# radio-v4_0.net
KiCad netlist of a schematic drawn in EAGLE
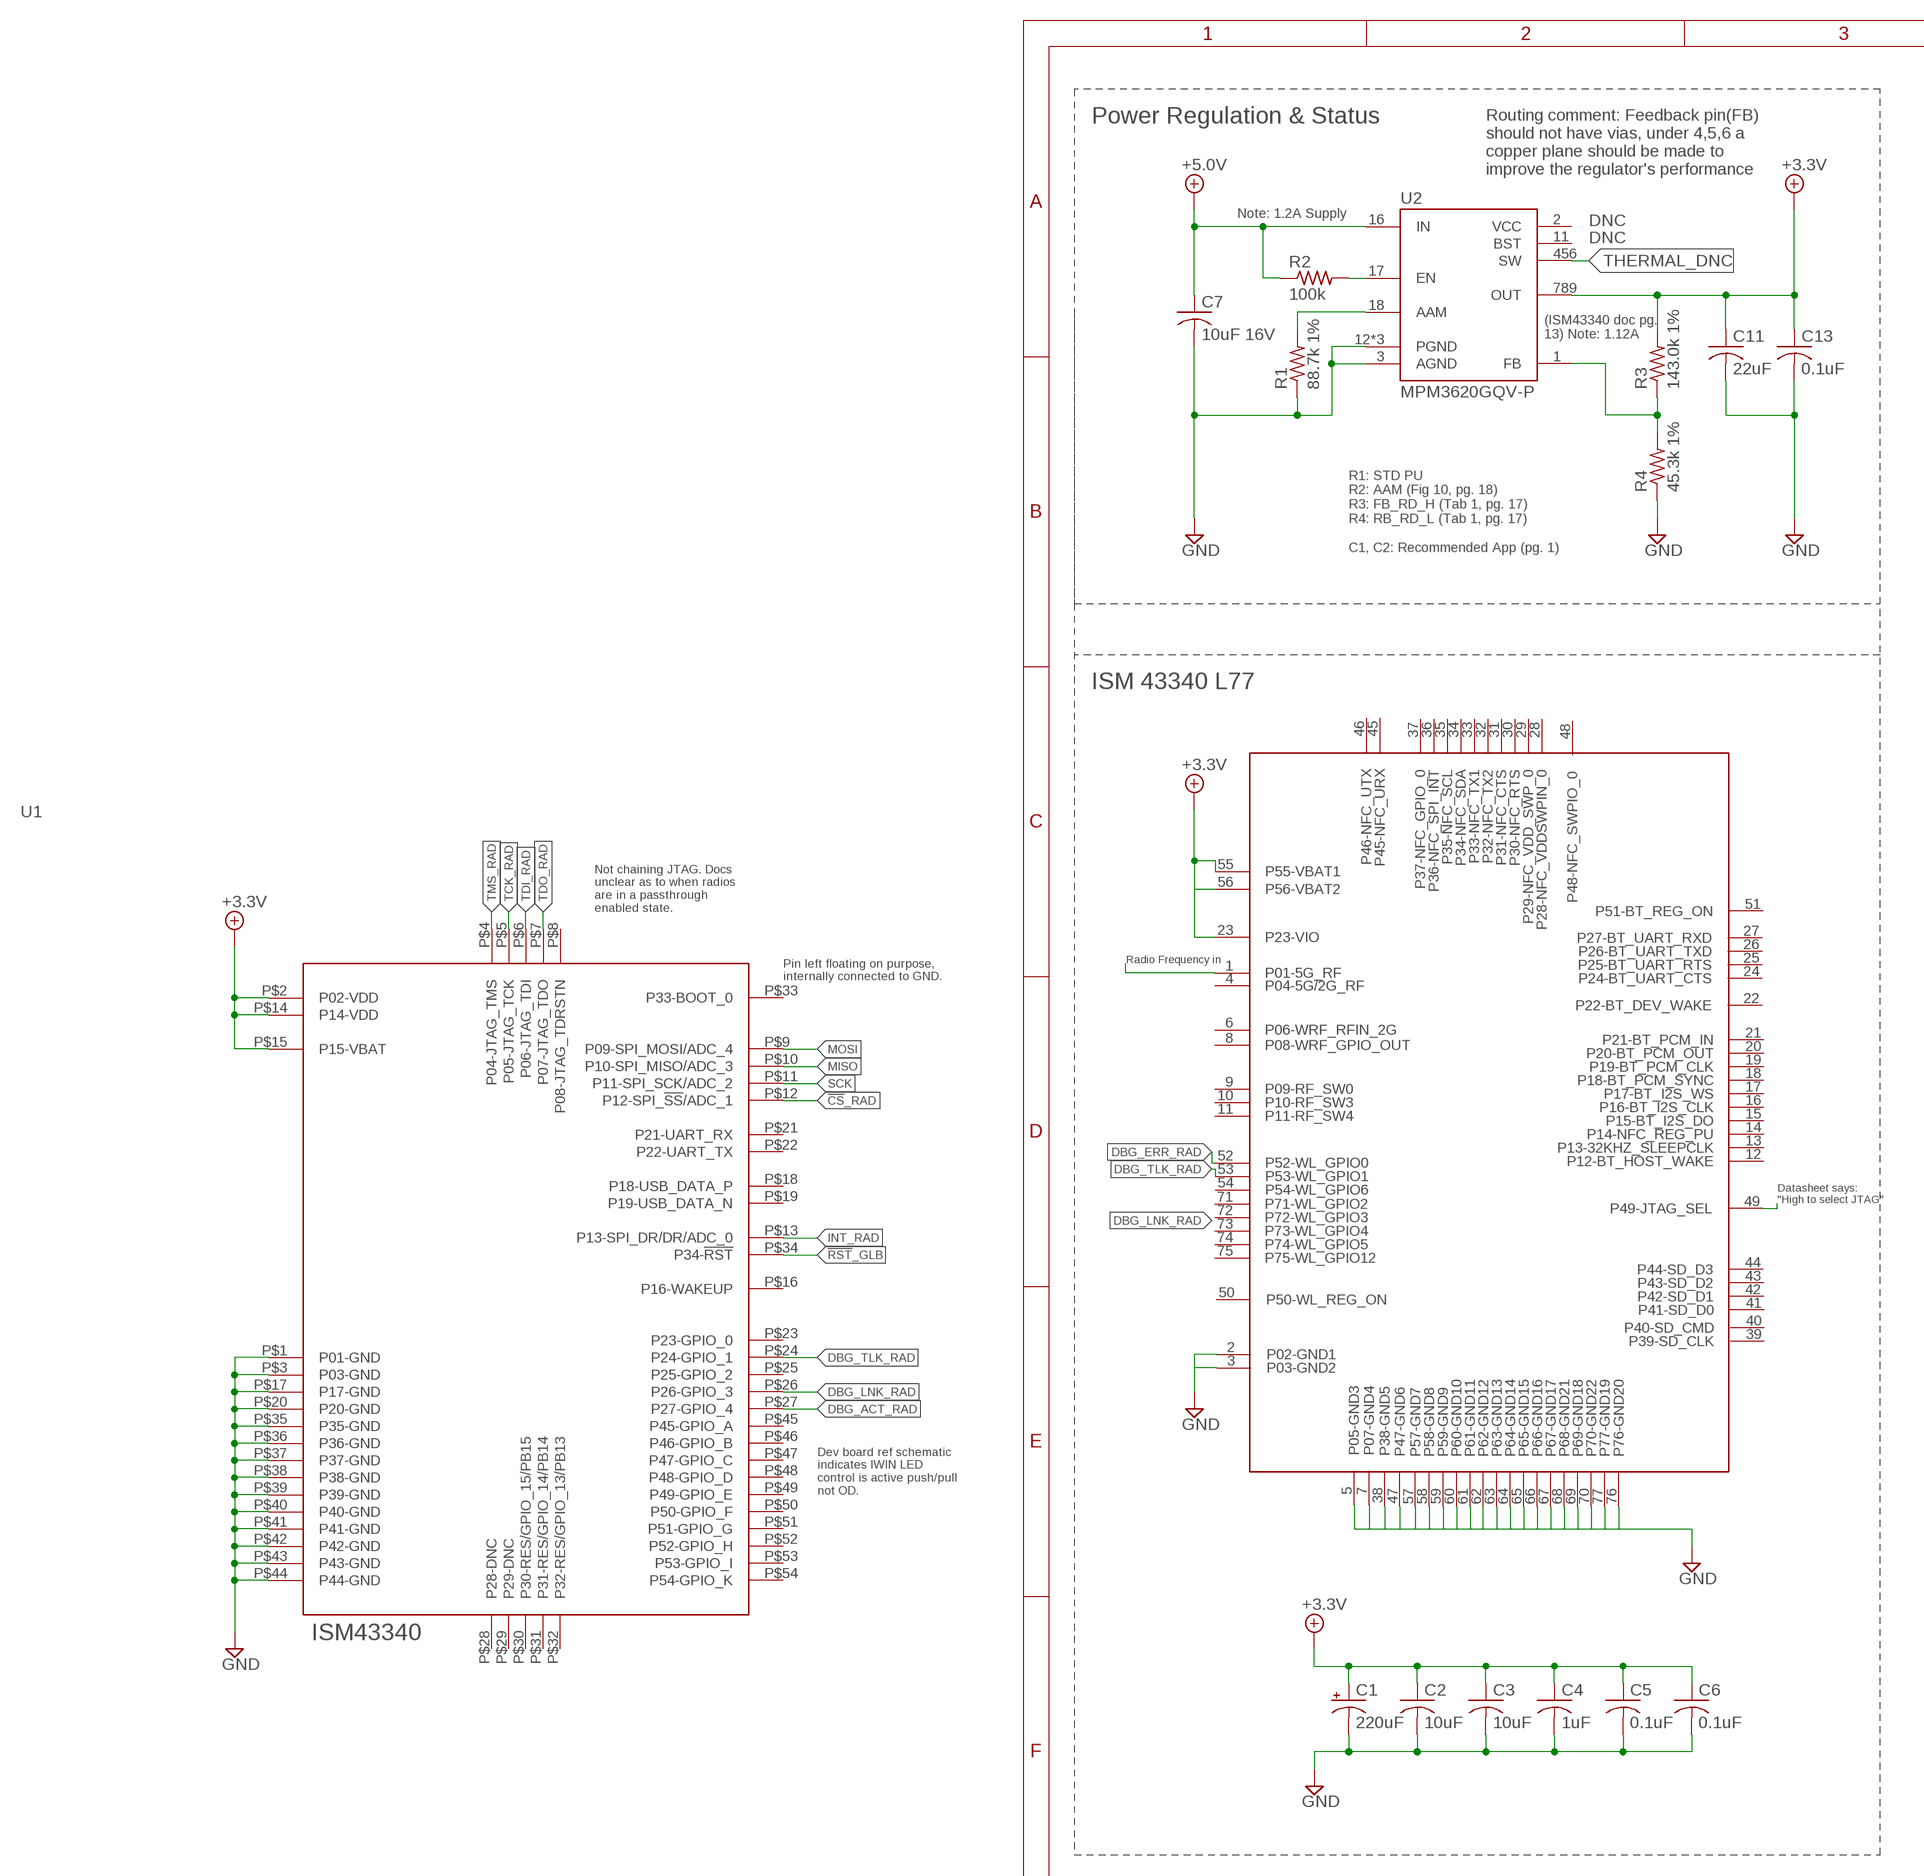
[diagram p0: schematic, sheet 1, part 1 of 2]
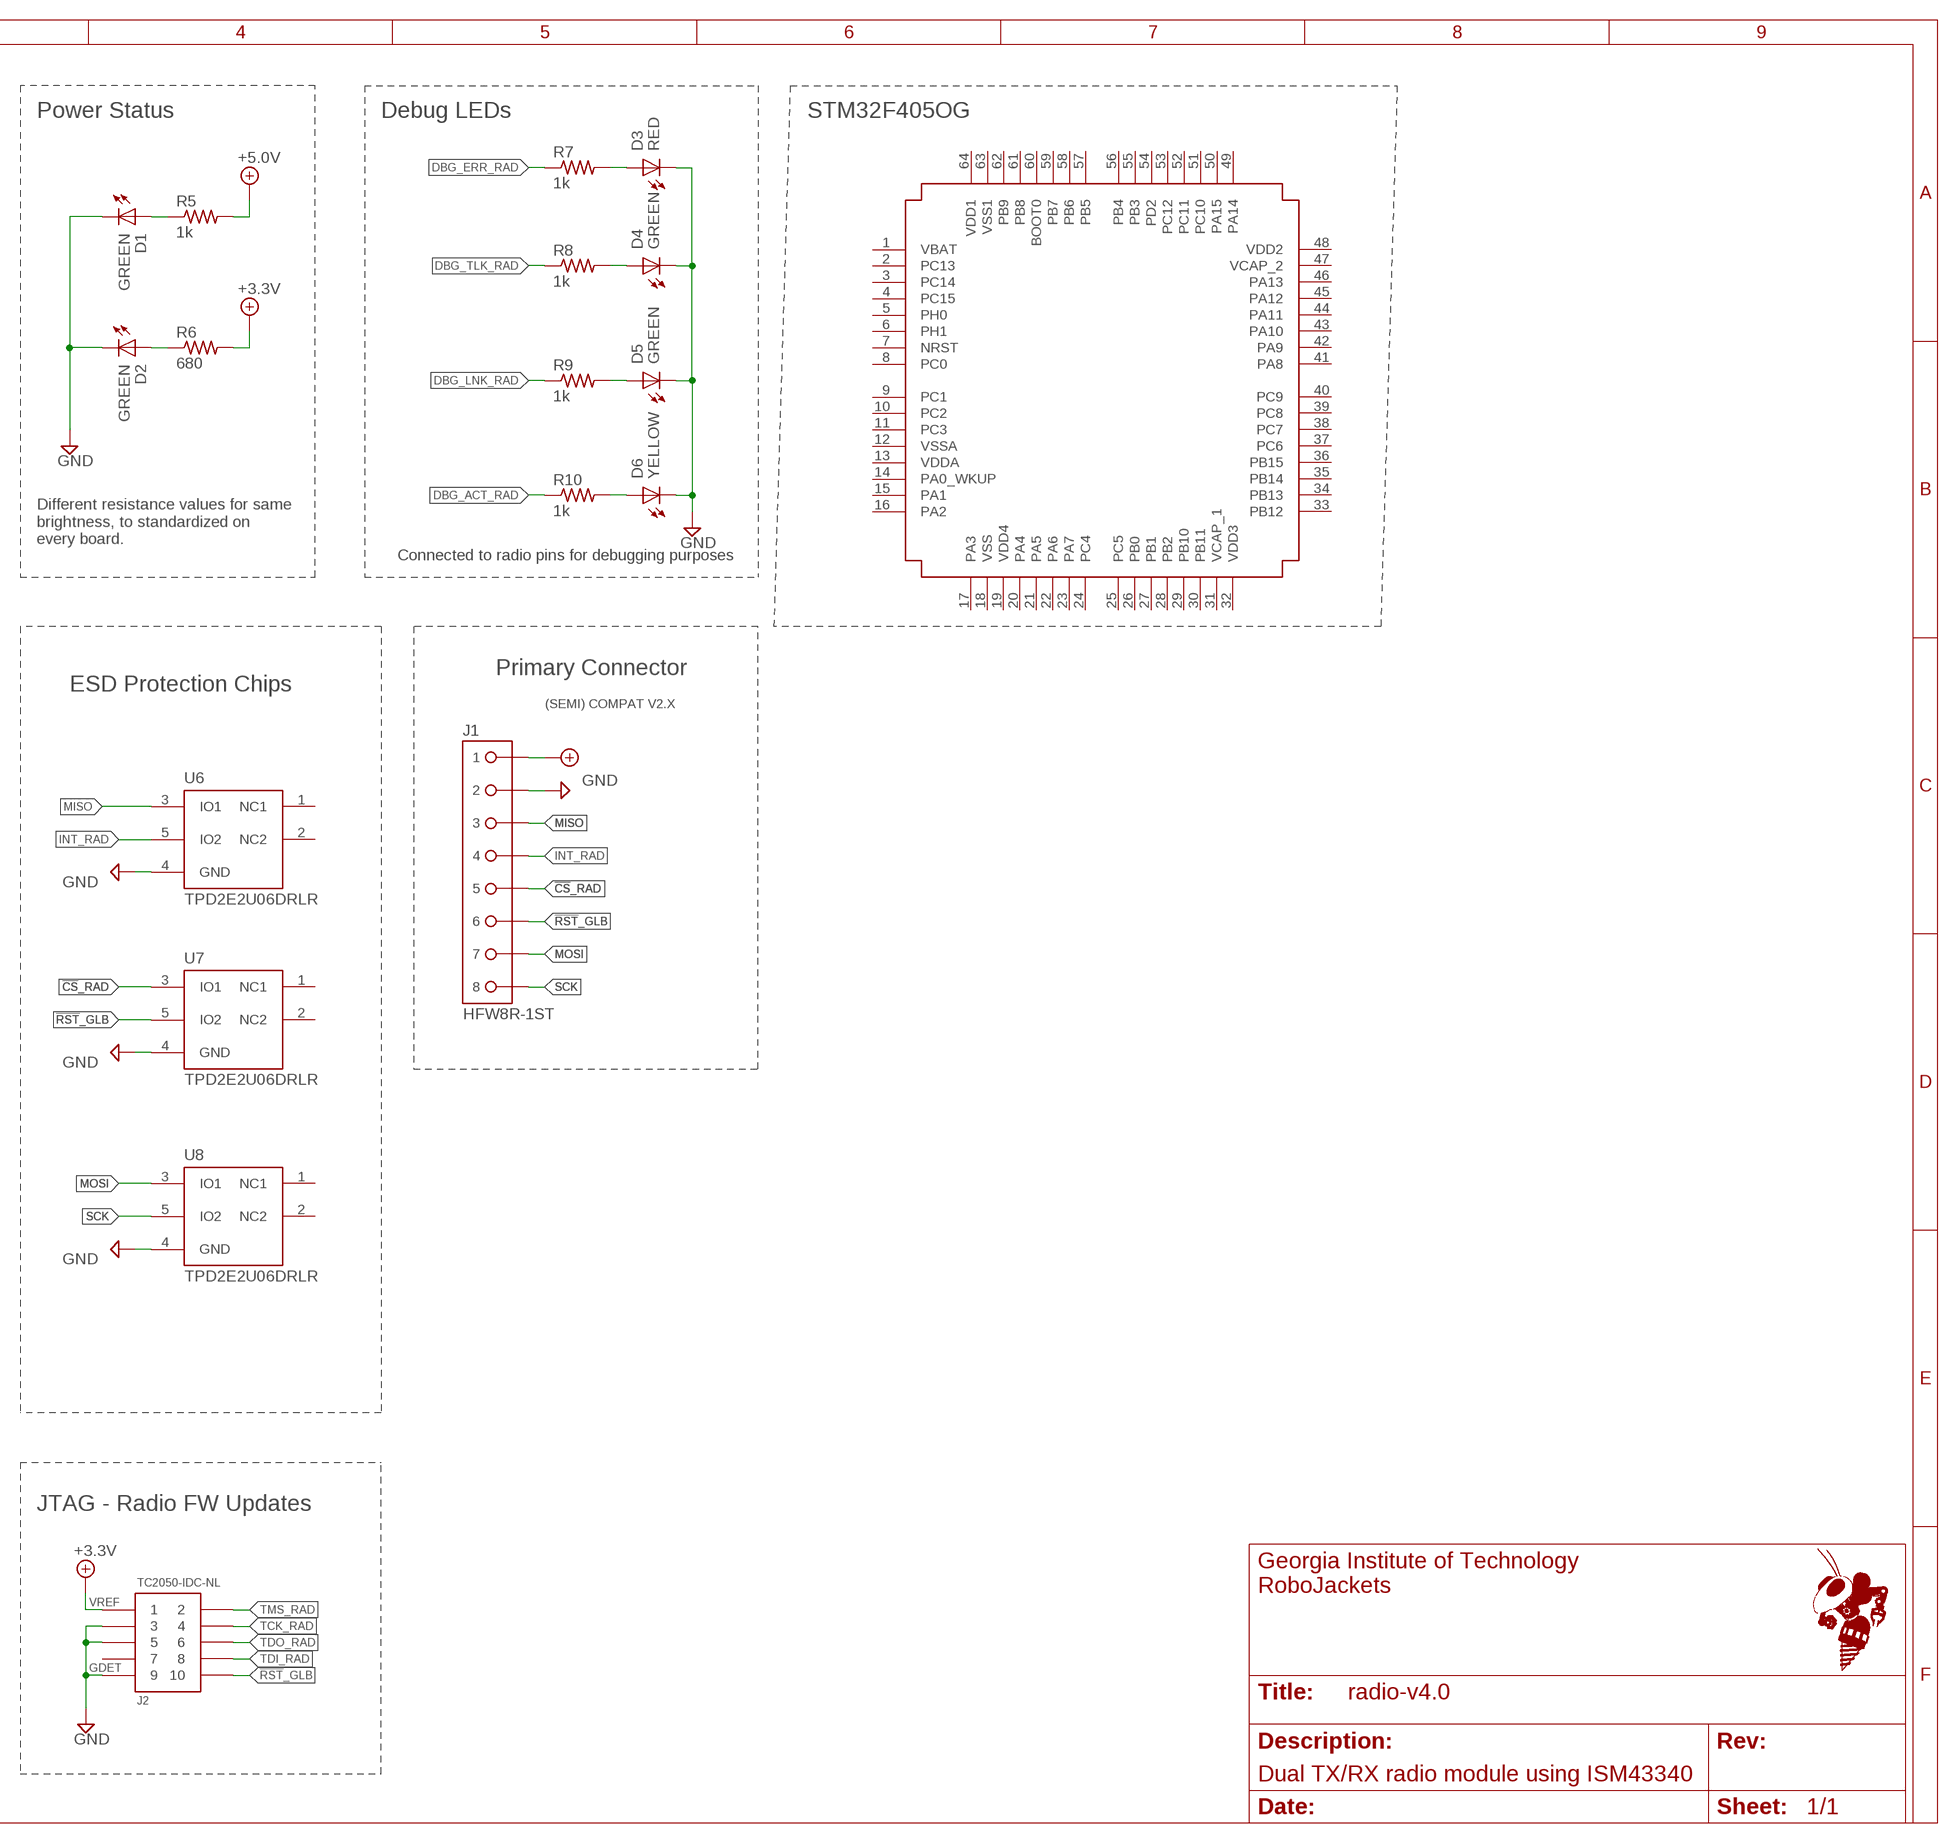
[diagram p1: schematic, sheet 1, part 2 of 2]

(export (version "E")
  (design (tool "Eeschema 10.0.6"))
  (components
    (comp (ref "C1")
      (value "220uF")
      (footprint "eagle-import:ECA-0JM221-HGT_HORIZ")
      (libsource (lib "eagle-import") (part "ECA-0JM221"))
    )
    (comp (ref "C2")
      (value "10uF")
      (footprint "eagle-import:C0805")
      (libsource (lib "eagle-import") (part "C-USC0805"))
    )
    (comp (ref "C3")
      (value "10uF")
      (footprint "eagle-import:C0805")
      (libsource (lib "eagle-import") (part "C-USC0805"))
    )
    (comp (ref "C4")
      (value "1uF")
      (footprint "eagle-import:C0603")
      (libsource (lib "eagle-import") (part "C-USC0603"))
    )
    (comp (ref "C5")
      (value "0.1uF")
      (footprint "eagle-import:C0603")
      (libsource (lib "eagle-import") (part "C-USC0603"))
    )
    (comp (ref "C6")
      (value "0.1uF")
      (footprint "eagle-import:C0603")
      (libsource (lib "eagle-import") (part "C-USC0603"))
    )
    (comp (ref "C7")
      (value "10uF 16V")
      (footprint "eagle-import:C1210")
      (libsource (lib "eagle-import") (part "C-USC1210"))
    )
    (comp (ref "C11")
      (value "22uF")
      (footprint "eagle-import:C1210")
      (libsource (lib "eagle-import") (part "C-USC1210"))
    )
    (comp (ref "C13")
      (value "0.1uF")
      (footprint "eagle-import:C0603")
      (libsource (lib "eagle-import") (part "C-USC0603"))
    )
    (comp (ref "D1")
      (value "GREEN")
      (footprint "eagle-import:CHIP-LED0603")
      (fields (field (name "MPN") "LTST-C191KGKT"))
      (libsource (lib "eagle-import") (part "LED-SMD-GREEN"))
    )
    (comp (ref "D2")
      (value "GREEN")
      (footprint "eagle-import:CHIP-LED0603")
      (fields (field (name "MPN") "LTST-C191KGKT"))
      (libsource (lib "eagle-import") (part "LED-SMD-GREEN"))
    )
    (comp (ref "D3")
      (value "RED")
      (footprint "eagle-import:CHIP-LED0603")
      (fields (field (name "MPN") "LTST-C191KRKT"))
      (libsource (lib "eagle-import") (part "LED-SMD-RED"))
    )
    (comp (ref "D4")
      (value "GREEN")
      (footprint "eagle-import:CHIP-LED0603")
      (fields (field (name "MPN") "LTST-C191KGKT"))
      (libsource (lib "eagle-import") (part "LED-SMD-GREEN"))
    )
    (comp (ref "D5")
      (value "GREEN")
      (footprint "eagle-import:CHIP-LED0603")
      (fields (field (name "MPN") "LTST-C191KGKT"))
      (libsource (lib "eagle-import") (part "LED-SMD-GREEN"))
    )
    (comp (ref "D6")
      (value "YELLOW")
      (footprint "eagle-import:CHIP-LED0603")
      (fields (field (name "MPN") "LTST-C191KSKT"))
      (libsource (lib "eagle-import") (part "LED-SMD-YELLOW"))
    )
    (comp (ref "J1")
      (value "HFW8R-1ST")
      (footprint "eagle-import:HFW8R-1ST")
      (fields (field (name "MPN") "HFW8R-1STE1LF"))
      (libsource (lib "eagle-import") (part "HFW8R-1ST"))
    )
    (comp (ref "J2")
      (value "TC2050-IDC-NL")
      (footprint "eagle-import:TC2050-IDC-NL")
      (libsource (lib "eagle-import") (part "TC2050-IDC-NL"))
    )
    (comp (ref "R1")
      (value "88.7k 1%")
      (footprint "eagle-import:R0603")
      (libsource (lib "eagle-import") (part "resistor_348_R-US_R0603"))
    )
    (comp (ref "R2")
      (value "100k")
      (footprint "eagle-import:R0603")
      (libsource (lib "eagle-import") (part "resistor_348_R-US_R0603"))
    )
    (comp (ref "R3")
      (value "143.0k 1%")
      (footprint "eagle-import:R0603")
      (libsource (lib "eagle-import") (part "R-US_R0603"))
    )
    (comp (ref "R4")
      (value "45.3k 1%")
      (footprint "eagle-import:R0603")
      (libsource (lib "eagle-import") (part "R-US_R0603"))
    )
    (comp (ref "R5")
      (value "1k")
      (footprint "eagle-import:R0603")
      (libsource (lib "eagle-import") (part "resistor_348_R-US_R0603"))
    )
    (comp (ref "R6")
      (value "680")
      (footprint "eagle-import:R0603")
      (libsource (lib "eagle-import") (part "resistor_348_R-US_R0603"))
    )
    (comp (ref "R7")
      (value "1k")
      (footprint "eagle-import:R0603")
      (libsource (lib "eagle-import") (part "resistor_348_R-US_R0603"))
    )
    (comp (ref "R8")
      (value "1k")
      (footprint "eagle-import:R0603")
      (libsource (lib "eagle-import") (part "resistor_348_R-US_R0603"))
    )
    (comp (ref "R9")
      (value "1k")
      (footprint "eagle-import:R0603")
      (libsource (lib "eagle-import") (part "resistor_348_R-US_R0603"))
    )
    (comp (ref "R10")
      (value "1k")
      (footprint "eagle-import:R0603")
      (libsource (lib "eagle-import") (part "resistor_348_R-US_R0603"))
    )
    (comp (ref "U$1")
      (value "ISM43340-L77")
      (footprint "eagle-import:ISM43340-L77")
      (libsource (lib "eagle-import") (part "ISM43340-L77"))
    )
    (comp (ref "U$2")
      (value "STM32F405OG-LQFP64")
      (footprint "eagle-import:STM32F405OG-LQFP64")
      (libsource (lib "eagle-import") (part "STM32F405OG-LQFP64"))
    )
    (comp (ref "U1")
      (value "ISM43340")
      (footprint "eagle-import:ISM43340")
      (libsource (lib "eagle-import") (part "ISM43340"))
    )
    (comp (ref "U2")
      (value "MPM3620GQV-P")
      (footprint "eagle-import:MPM3620GQV-P")
      (libsource (lib "eagle-import") (part "MPM3620GQV-P"))
    )
    (comp (ref "U6")
      (value "TPD2E2U06DRLR")
      (footprint "eagle-import:SOT-553")
      (libsource (lib "eagle-import") (part "TPD2E2U06DRLR"))
    )
    (comp (ref "U7")
      (value "TPD2E2U06DRLR")
      (footprint "eagle-import:SOT-553")
      (libsource (lib "eagle-import") (part "TPD2E2U06DRLR"))
    )
    (comp (ref "U8")
      (value "TPD2E2U06DRLR")
      (footprint "eagle-import:SOT-553")
      (libsource (lib "eagle-import") (part "TPD2E2U06DRLR"))
    )
  )
  (nets
    (net (code "1") (name "+3.3V") (class "Default")
      (node (ref "C1") (pin "P$1") (pinfunction "+_P$1") (pintype "passive"))
      (node (ref "C11") (pin "1") (pinfunction "1_1") (pintype "passive"))
      (node (ref "C13") (pin "1") (pinfunction "1_1") (pintype "passive"))
      (node (ref "C2") (pin "1") (pinfunction "1_1") (pintype "passive"))
      (node (ref "C3") (pin "1") (pinfunction "1_1") (pintype "passive"))
      (node (ref "C4") (pin "1") (pinfunction "1_1") (pintype "passive"))
      (node (ref "C5") (pin "1") (pinfunction "1_1") (pintype "passive"))
      (node (ref "C6") (pin "1") (pinfunction "1_1") (pintype "passive"))
      (node (ref "J2") (pin "1") (pinfunction "1_1") (pintype "bidirectional"))
      (node (ref "R3") (pin "2") (pinfunction "2_2") (pintype "passive"))
      (node (ref "R6") (pin "2") (pinfunction "2_2") (pintype "passive"))
      (node (ref "U$1") (pin "23") (pinfunction "P23-VIO_23") (pintype "bidirectional"))
      (node (ref "U$1") (pin "55") (pinfunction "P55-VBAT1_55") (pintype "bidirectional"))
      (node (ref "U$1") (pin "56") (pinfunction "P56-VBAT2_56") (pintype "bidirectional"))
      (node (ref "U1") (pin "P$14") (pinfunction "P14-VDD_P$14") (pintype "bidirectional"))
      (node (ref "U1") (pin "P$15") (pinfunction "P15-VBAT_P$15") (pintype "bidirectional"))
      (node (ref "U1") (pin "P$2") (pinfunction "P02-VDD_P$2") (pintype "bidirectional"))
      (node (ref "U2") (pin "789") (pinfunction "OUT_789") (pintype "bidirectional"))
    )
    (net (code "2") (name "+5.0V") (class "Default")
      (node (ref "C7") (pin "1") (pinfunction "1_1") (pintype "passive"))
      (node (ref "J1") (pin "1") (pinfunction "1_1") (pintype "passive"))
      (node (ref "R2") (pin "1") (pinfunction "1_1") (pintype "passive"))
      (node (ref "R5") (pin "2") (pinfunction "2_2") (pintype "passive"))
      (node (ref "U2") (pin "16") (pinfunction "IN_16") (pintype "bidirectional"))
    )
    (net (code "3") (name "/~{CS}_RAD") (class "Default")
      (node (ref "J1") (pin "5") (pinfunction "5_5") (pintype "passive"))
      (node (ref "U1") (pin "P$12") (pinfunction "P12-SPI_~{SS}/ADC_1_P$12") (pintype "bidirectional"))
      (node (ref "U7") (pin "3") (pinfunction "IO1_3") (pintype "bidirectional"))
    )
    (net (code "4") (name "/~{RST}_GLB") (class "Default")
      (node (ref "J1") (pin "6") (pinfunction "6_6") (pintype "passive"))
      (node (ref "J2") (pin "10") (pinfunction "10_10") (pintype "bidirectional"))
      (node (ref "U1") (pin "P$34") (pinfunction "P34-~{RST}_P$34") (pintype "bidirectional"))
      (node (ref "U7") (pin "5") (pinfunction "IO2_5") (pintype "bidirectional"))
    )
    (net (code "5") (name "DBG_ACT_RAD") (class "Default")
      (node (ref "R10") (pin "1") (pinfunction "1_1") (pintype "passive"))
      (node (ref "U1") (pin "P$27") (pinfunction "P27-GPIO_4_P$27") (pintype "bidirectional"))
    )
    (net (code "6") (name "DBG_ERR_RAD") (class "Default")
      (node (ref "R7") (pin "1") (pinfunction "1_1") (pintype "passive"))
      (node (ref "U$1") (pin "52") (pinfunction "P52-WL_GPIO0_52") (pintype "bidirectional"))
    )
    (net (code "7") (name "DBG_LNK_RAD") (class "Default")
      (node (ref "R9") (pin "1") (pinfunction "1_1") (pintype "passive"))
      (node (ref "U1") (pin "P$26") (pinfunction "P26-GPIO_3_P$26") (pintype "bidirectional"))
    )
    (net (code "8") (name "DBG_TLK_RAD") (class "Default")
      (node (ref "R8") (pin "1") (pinfunction "1_1") (pintype "passive"))
      (node (ref "U1") (pin "P$24") (pinfunction "P24-GPIO_1_P$24") (pintype "bidirectional"))
    )
    (net (code "9") (name "GND") (class "Default")
      (node (ref "C1") (pin "P$2") (pinfunction "-_P$2") (pintype "passive"))
      (node (ref "C11") (pin "2") (pinfunction "2_2") (pintype "passive"))
      (node (ref "C13") (pin "2") (pinfunction "2_2") (pintype "passive"))
      (node (ref "C2") (pin "2") (pinfunction "2_2") (pintype "passive"))
      (node (ref "C3") (pin "2") (pinfunction "2_2") (pintype "passive"))
      (node (ref "C4") (pin "2") (pinfunction "2_2") (pintype "passive"))
      (node (ref "C5") (pin "2") (pinfunction "2_2") (pintype "passive"))
      (node (ref "C6") (pin "2") (pinfunction "2_2") (pintype "passive"))
      (node (ref "C7") (pin "2") (pinfunction "2_2") (pintype "passive"))
      (node (ref "D1") (pin "C") (pinfunction "K_C") (pintype "passive"))
      (node (ref "D2") (pin "C") (pinfunction "K_C") (pintype "passive"))
      (node (ref "D3") (pin "C") (pinfunction "K_C") (pintype "passive"))
      (node (ref "D4") (pin "C") (pinfunction "K_C") (pintype "passive"))
      (node (ref "D5") (pin "C") (pinfunction "K_C") (pintype "passive"))
      (node (ref "D6") (pin "C") (pinfunction "K_C") (pintype "passive"))
      (node (ref "J1") (pin "2") (pinfunction "2_2") (pintype "passive"))
      (node (ref "J2") (pin "3") (pinfunction "3_3") (pintype "bidirectional"))
      (node (ref "J2") (pin "5") (pinfunction "5_5") (pintype "bidirectional"))
      (node (ref "J2") (pin "9") (pinfunction "9_9") (pintype "bidirectional"))
      (node (ref "R1") (pin "1") (pinfunction "1_1") (pintype "passive"))
      (node (ref "R4") (pin "1") (pinfunction "1_1") (pintype "passive"))
      (node (ref "U$1") (pin "2") (pinfunction "P02-GND1_2") (pintype "bidirectional"))
      (node (ref "U$1") (pin "3") (pinfunction "P03-GND2_3") (pintype "bidirectional"))
      (node (ref "U$1") (pin "76") (pinfunction "P76-GND20_76") (pintype "bidirectional"))
      (node (ref "U$1") (pin "77") (pinfunction "P77-GND19_77") (pintype "bidirectional"))
      (node (ref "U1") (pin "P$1") (pinfunction "P01-GND_P$1") (pintype "bidirectional"))
      (node (ref "U1") (pin "P$17") (pinfunction "P17-GND_P$17") (pintype "bidirectional"))
      (node (ref "U1") (pin "P$20") (pinfunction "P20-GND_P$20") (pintype "bidirectional"))
      (node (ref "U1") (pin "P$3") (pinfunction "P03-GND_P$3") (pintype "bidirectional"))
      (node (ref "U1") (pin "P$35") (pinfunction "P35-GND_P$35") (pintype "bidirectional"))
      (node (ref "U1") (pin "P$36") (pinfunction "P36-GND_P$36") (pintype "bidirectional"))
      (node (ref "U1") (pin "P$37") (pinfunction "P37-GND_P$37") (pintype "bidirectional"))
      (node (ref "U1") (pin "P$38") (pinfunction "P38-GND_P$38") (pintype "bidirectional"))
      (node (ref "U1") (pin "P$39") (pinfunction "P39-GND_P$39") (pintype "bidirectional"))
      (node (ref "U1") (pin "P$40") (pinfunction "P40-GND_P$40") (pintype "bidirectional"))
      (node (ref "U1") (pin "P$41") (pinfunction "P41-GND_P$41") (pintype "bidirectional"))
      (node (ref "U1") (pin "P$42") (pinfunction "P42-GND_P$42") (pintype "bidirectional"))
      (node (ref "U1") (pin "P$43") (pinfunction "P43-GND_P$43") (pintype "bidirectional"))
      (node (ref "U1") (pin "P$44") (pinfunction "P44-GND_P$44") (pintype "bidirectional"))
      (node (ref "U2") (pin "12") (pinfunction "PGND_12") (pintype "bidirectional"))
      (node (ref "U2") (pin "13") (pinfunction "PGND_13") (pintype "bidirectional"))
      (node (ref "U2") (pin "14") (pinfunction "PGND_14") (pintype "bidirectional"))
      (node (ref "U2") (pin "3") (pinfunction "AGND_3") (pintype "bidirectional"))
      (node (ref "U6") (pin "4") (pinfunction "GND_4") (pintype "power_in"))
      (node (ref "U7") (pin "4") (pinfunction "GND_4") (pintype "power_in"))
      (node (ref "U8") (pin "4") (pinfunction "GND_4") (pintype "power_in"))
    )
    (net (code "10") (name "INT_RAD") (class "Default")
      (node (ref "J1") (pin "4") (pinfunction "4_4") (pintype "passive"))
      (node (ref "U1") (pin "P$13") (pinfunction "P13-SPI_DR/DR/ADC_0_P$13") (pintype "bidirectional"))
      (node (ref "U6") (pin "5") (pinfunction "IO2_5") (pintype "bidirectional"))
    )
    (net (code "11") (name "MISO") (class "Default")
      (node (ref "J1") (pin "3") (pinfunction "3_3") (pintype "passive"))
      (node (ref "U1") (pin "P$10") (pinfunction "P10-SPI_MISO/ADC_3_P$10") (pintype "bidirectional"))
      (node (ref "U6") (pin "3") (pinfunction "IO1_3") (pintype "bidirectional"))
    )
    (net (code "12") (name "MOSI") (class "Default")
      (node (ref "J1") (pin "7") (pinfunction "7_7") (pintype "passive"))
      (node (ref "U1") (pin "P$9") (pinfunction "P09-SPI_MOSI/ADC_4_P$9") (pintype "bidirectional"))
      (node (ref "U8") (pin "3") (pinfunction "IO1_3") (pintype "bidirectional"))
    )
    (net (code "13") (name "Net-(D1-PadA)") (class "Default")
      (node (ref "D1") (pin "A") (pinfunction "A_A") (pintype "passive"))
      (node (ref "R5") (pin "1") (pinfunction "1_1") (pintype "passive"))
    )
    (net (code "14") (name "Net-(D2-PadA)") (class "Default")
      (node (ref "D2") (pin "A") (pinfunction "A_A") (pintype "passive"))
      (node (ref "R6") (pin "1") (pinfunction "1_1") (pintype "passive"))
    )
    (net (code "15") (name "Net-(D3-PadA)") (class "Default")
      (node (ref "D3") (pin "A") (pinfunction "A_A") (pintype "passive"))
      (node (ref "R7") (pin "2") (pinfunction "2_2") (pintype "passive"))
    )
    (net (code "16") (name "Net-(D4-PadA)") (class "Default")
      (node (ref "D4") (pin "A") (pinfunction "A_A") (pintype "passive"))
      (node (ref "R8") (pin "2") (pinfunction "2_2") (pintype "passive"))
    )
    (net (code "17") (name "Net-(D5-PadA)") (class "Default")
      (node (ref "D5") (pin "A") (pinfunction "A_A") (pintype "passive"))
      (node (ref "R9") (pin "2") (pinfunction "2_2") (pintype "passive"))
    )
    (net (code "18") (name "Net-(D6-PadA)") (class "Default")
      (node (ref "D6") (pin "A") (pinfunction "A_A") (pintype "passive"))
      (node (ref "R10") (pin "2") (pinfunction "2_2") (pintype "passive"))
    )
    (net (code "19") (name "Net-(U$1-P05-GND3)") (class "Default")
      (node (ref "U$1") (pin "38") (pinfunction "P38-GND5_38") (pintype "bidirectional"))
      (node (ref "U$1") (pin "47") (pinfunction "P47-GND6_47") (pintype "bidirectional"))
      (node (ref "U$1") (pin "5") (pinfunction "P05-GND3_5") (pintype "bidirectional"))
      (node (ref "U$1") (pin "57") (pinfunction "P57-GND7_57") (pintype "bidirectional"))
      (node (ref "U$1") (pin "58") (pinfunction "P58-GND8_58") (pintype "bidirectional"))
      (node (ref "U$1") (pin "59") (pinfunction "P59-GND9_59") (pintype "bidirectional"))
      (node (ref "U$1") (pin "60") (pinfunction "P60-GND10_60") (pintype "bidirectional"))
      (node (ref "U$1") (pin "61") (pinfunction "P61-GND11_61") (pintype "bidirectional"))
      (node (ref "U$1") (pin "62") (pinfunction "P62-GND12_62") (pintype "bidirectional"))
      (node (ref "U$1") (pin "63") (pinfunction "P63-GND13_63") (pintype "bidirectional"))
      (node (ref "U$1") (pin "64") (pinfunction "P64-GND14_64") (pintype "bidirectional"))
      (node (ref "U$1") (pin "65") (pinfunction "P65-GND15_65") (pintype "bidirectional"))
      (node (ref "U$1") (pin "66") (pinfunction "P66-GND16_66") (pintype "bidirectional"))
      (node (ref "U$1") (pin "67") (pinfunction "P67-GND17_67") (pintype "bidirectional"))
      (node (ref "U$1") (pin "68") (pinfunction "P68-GND21_68") (pintype "bidirectional"))
      (node (ref "U$1") (pin "69") (pinfunction "P69-GND18_69") (pintype "bidirectional"))
      (node (ref "U$1") (pin "7") (pinfunction "P07-GND4_7") (pintype "bidirectional"))
      (node (ref "U$1") (pin "70") (pinfunction "P70-GND22_70") (pintype "bidirectional"))
    )
    (net (code "20") (name "Net-(U2-AAM)") (class "Default")
      (node (ref "R1") (pin "2") (pinfunction "2_2") (pintype "passive"))
      (node (ref "U2") (pin "18") (pinfunction "AAM_18") (pintype "bidirectional"))
    )
    (net (code "21") (name "Net-(U2-EN)") (class "Default")
      (node (ref "R2") (pin "2") (pinfunction "2_2") (pintype "passive"))
      (node (ref "U2") (pin "17") (pinfunction "EN_17") (pintype "bidirectional"))
    )
    (net (code "22") (name "Net-(U2-FB)") (class "Default")
      (node (ref "R3") (pin "1") (pinfunction "1_1") (pintype "passive"))
      (node (ref "R4") (pin "2") (pinfunction "2_2") (pintype "passive"))
      (node (ref "U2") (pin "1") (pinfunction "FB_1") (pintype "bidirectional"))
    )
    (net (code "23") (name "SCK") (class "Default")
      (node (ref "J1") (pin "8") (pinfunction "8_8") (pintype "passive"))
      (node (ref "U1") (pin "P$11") (pinfunction "P11-SPI_SCK/ADC_2_P$11") (pintype "bidirectional"))
      (node (ref "U8") (pin "5") (pinfunction "IO2_5") (pintype "bidirectional"))
    )
    (net (code "24") (name "TCK_RAD") (class "Default")
      (node (ref "J2") (pin "4") (pinfunction "4_4") (pintype "bidirectional"))
      (node (ref "U1") (pin "P$5") (pinfunction "P05-JTAG_TCK_P$5") (pintype "bidirectional"))
    )
    (net (code "25") (name "TDI_RAD") (class "Default")
      (node (ref "J2") (pin "8") (pinfunction "8_8") (pintype "bidirectional"))
      (node (ref "U1") (pin "P$6") (pinfunction "P06-JTAG_TDI_P$6") (pintype "bidirectional"))
    )
    (net (code "26") (name "TDO_RAD") (class "Default")
      (node (ref "J2") (pin "6") (pinfunction "6_6") (pintype "bidirectional"))
      (node (ref "U1") (pin "P$7") (pinfunction "P07-JTAG_TDO_P$7") (pintype "bidirectional"))
    )
    (net (code "27") (name "THERMAL_DNC") (class "Default")
      (node (ref "U2") (pin "456") (pinfunction "SW_456") (pintype "bidirectional"))
    )
    (net (code "28") (name "TMS_RAD") (class "Default")
      (node (ref "J2") (pin "2") (pinfunction "2_2") (pintype "bidirectional"))
      (node (ref "U1") (pin "P$4") (pinfunction "P04-JTAG_TMS_P$4") (pintype "bidirectional"))
    )
    (net (code "29") (name "unconnected-(J2-Pad7)") (class "Default")
      (node (ref "J2") (pin "7") (pinfunction "7_7") (pintype "bidirectional"))
    )
    (net (code "30") (name "unconnected-(U$1-P01-5G_RF-Pad1)") (class "Default")
      (node (ref "U$1") (pin "1") (pinfunction "P01-5G_RF_1") (pintype "bidirectional"))
    )
    (net (code "31") (name "unconnected-(U$1-P04-5G{slash}2G_RF-Pad4)") (class "Default")
      (node (ref "U$1") (pin "4") (pinfunction "P04-5G/2G_RF_4") (pintype "bidirectional"))
    )
    (net (code "32") (name "unconnected-(U$1-P06-WRF_RFIN_2G-Pad6)") (class "Default")
      (node (ref "U$1") (pin "6") (pinfunction "P06-WRF_RFIN_2G_6") (pintype "bidirectional"))
    )
    (net (code "33") (name "unconnected-(U$1-P08-WRF_GPIO_OUT-Pad8)") (class "Default")
      (node (ref "U$1") (pin "8") (pinfunction "P08-WRF_GPIO_OUT_8") (pintype "bidirectional"))
    )
    (net (code "34") (name "unconnected-(U$1-P09-RF_SW0-Pad9)") (class "Default")
      (node (ref "U$1") (pin "9") (pinfunction "P09-RF_SW0_9") (pintype "bidirectional"))
    )
    (net (code "35") (name "unconnected-(U$1-P10-RF_SW3-Pad10)") (class "Default")
      (node (ref "U$1") (pin "10") (pinfunction "P10-RF_SW3_10") (pintype "bidirectional"))
    )
    (net (code "36") (name "unconnected-(U$1-P11-RF_SW4-Pad11)") (class "Default")
      (node (ref "U$1") (pin "11") (pinfunction "P11-RF_SW4_11") (pintype "bidirectional"))
    )
    (net (code "37") (name "unconnected-(U$1-P12-BT_HOST_WAKE-Pad12)") (class "Default")
      (node (ref "U$1") (pin "12") (pinfunction "P12-BT_HOST_WAKE_12") (pintype "bidirectional"))
    )
    (net (code "38") (name "unconnected-(U$1-P13-32KHZ_SLEEPCLK-Pad13)") (class "Default")
      (node (ref "U$1") (pin "13") (pinfunction "P13-32KHZ_SLEEPCLK_13") (pintype "bidirectional"))
    )
    (net (code "39") (name "unconnected-(U$1-P14-NFC_REG_PU-Pad14)") (class "Default")
      (node (ref "U$1") (pin "14") (pinfunction "P14-NFC_REG_PU_14") (pintype "bidirectional"))
    )
    (net (code "40") (name "unconnected-(U$1-P15-BT_I2S_DO-Pad15)") (class "Default")
      (node (ref "U$1") (pin "15") (pinfunction "P15-BT_I2S_DO_15") (pintype "bidirectional"))
    )
    (net (code "41") (name "unconnected-(U$1-P16-BT_I2S_CLK-Pad16)") (class "Default")
      (node (ref "U$1") (pin "16") (pinfunction "P16-BT_I2S_CLK_16") (pintype "bidirectional"))
    )
    (net (code "42") (name "unconnected-(U$1-P17-BT_I2S_WS-Pad17)") (class "Default")
      (node (ref "U$1") (pin "17") (pinfunction "P17-BT_I2S_WS_17") (pintype "bidirectional"))
    )
    (net (code "43") (name "unconnected-(U$1-P18-BT_PCM_SYNC-Pad18)") (class "Default")
      (node (ref "U$1") (pin "18") (pinfunction "P18-BT_PCM_SYNC_18") (pintype "bidirectional"))
    )
    (net (code "44") (name "unconnected-(U$1-P19-BT_PCM_CLK-Pad19)") (class "Default")
      (node (ref "U$1") (pin "19") (pinfunction "P19-BT_PCM_CLK_19") (pintype "bidirectional"))
    )
    (net (code "45") (name "unconnected-(U$1-P20-BT_PCM_OUT-Pad20)") (class "Default")
      (node (ref "U$1") (pin "20") (pinfunction "P20-BT_PCM_OUT_20") (pintype "bidirectional"))
    )
    (net (code "46") (name "unconnected-(U$1-P21-BT_PCM_IN-Pad21)") (class "Default")
      (node (ref "U$1") (pin "21") (pinfunction "P21-BT_PCM_IN_21") (pintype "bidirectional"))
    )
    (net (code "47") (name "unconnected-(U$1-P22-BT_DEV_WAKE-Pad22)") (class "Default")
      (node (ref "U$1") (pin "22") (pinfunction "P22-BT_DEV_WAKE_22") (pintype "bidirectional"))
    )
    (net (code "48") (name "unconnected-(U$1-P24-BT_UART_CTS-Pad24)") (class "Default")
      (node (ref "U$1") (pin "24") (pinfunction "P24-BT_UART_CTS_24") (pintype "bidirectional"))
    )
    (net (code "49") (name "unconnected-(U$1-P25-BT_UART_RTS-Pad25)") (class "Default")
      (node (ref "U$1") (pin "25") (pinfunction "P25-BT_UART_RTS_25") (pintype "bidirectional"))
    )
    (net (code "50") (name "unconnected-(U$1-P26-BT_UART_TXD-Pad26)") (class "Default")
      (node (ref "U$1") (pin "26") (pinfunction "P26-BT_UART_TXD_26") (pintype "bidirectional"))
    )
    (net (code "51") (name "unconnected-(U$1-P27-BT_UART_RXD-Pad27)") (class "Default")
      (node (ref "U$1") (pin "27") (pinfunction "P27-BT_UART_RXD_27") (pintype "bidirectional"))
    )
    (net (code "52") (name "unconnected-(U$1-P28-NFC_VDDSWPIN_0-Pad28)") (class "Default")
      (node (ref "U$1") (pin "28") (pinfunction "P28-NFC_VDDSWPIN_0_28") (pintype "bidirectional"))
    )
    (net (code "53") (name "unconnected-(U$1-P29-NFC_VDD_SWP_0-Pad29)") (class "Default")
      (node (ref "U$1") (pin "29") (pinfunction "P29-NFC_VDD_SWP_0_29") (pintype "bidirectional"))
    )
    (net (code "54") (name "unconnected-(U$1-P30-NFC_RTS-Pad30)") (class "Default")
      (node (ref "U$1") (pin "30") (pinfunction "P30-NFC_RTS_30") (pintype "bidirectional"))
    )
    (net (code "55") (name "unconnected-(U$1-P31-NFC_CTS-Pad31)") (class "Default")
      (node (ref "U$1") (pin "31") (pinfunction "P31-NFC_CTS_31") (pintype "bidirectional"))
    )
    (net (code "56") (name "unconnected-(U$1-P32-NFC_TX2-Pad32)") (class "Default")
      (node (ref "U$1") (pin "32") (pinfunction "P32-NFC_TX2_32") (pintype "bidirectional"))
    )
    (net (code "57") (name "unconnected-(U$1-P33-NFC_TX1-Pad33)") (class "Default")
      (node (ref "U$1") (pin "33") (pinfunction "P33-NFC_TX1_33") (pintype "bidirectional"))
    )
    (net (code "58") (name "unconnected-(U$1-P34-NFC_SDA-Pad34)") (class "Default")
      (node (ref "U$1") (pin "34") (pinfunction "P34-NFC_SDA_34") (pintype "bidirectional"))
    )
    (net (code "59") (name "unconnected-(U$1-P35-NFC_SCL-Pad35)") (class "Default")
      (node (ref "U$1") (pin "35") (pinfunction "P35-NFC_SCL_35") (pintype "bidirectional"))
    )
    (net (code "60") (name "unconnected-(U$1-P36-NFC_SPI_INT-Pad36)") (class "Default")
      (node (ref "U$1") (pin "36") (pinfunction "P36-NFC_SPI_INT_36") (pintype "bidirectional"))
    )
    (net (code "61") (name "unconnected-(U$1-P37-NFC_GPIO_0-Pad37)") (class "Default")
      (node (ref "U$1") (pin "37") (pinfunction "P37-NFC_GPIO_0_37") (pintype "bidirectional"))
    )
    (net (code "62") (name "unconnected-(U$1-P39-SD_CLK-Pad39)") (class "Default")
      (node (ref "U$1") (pin "39") (pinfunction "P39-SD_CLK_39") (pintype "bidirectional"))
    )
    (net (code "63") (name "unconnected-(U$1-P40-SD_CMD-Pad40)") (class "Default")
      (node (ref "U$1") (pin "40") (pinfunction "P40-SD_CMD_40") (pintype "bidirectional"))
    )
    (net (code "64") (name "unconnected-(U$1-P41-SD_D0-Pad41)") (class "Default")
      (node (ref "U$1") (pin "41") (pinfunction "P41-SD_D0_41") (pintype "bidirectional"))
    )
    (net (code "65") (name "unconnected-(U$1-P42-SD_D1-Pad42)") (class "Default")
      (node (ref "U$1") (pin "42") (pinfunction "P42-SD_D1_42") (pintype "bidirectional"))
    )
    (net (code "66") (name "unconnected-(U$1-P43-SD_D2-Pad43)") (class "Default")
      (node (ref "U$1") (pin "43") (pinfunction "P43-SD_D2_43") (pintype "bidirectional"))
    )
    (net (code "67") (name "unconnected-(U$1-P44-SD_D3-Pad44)") (class "Default")
      (node (ref "U$1") (pin "44") (pinfunction "P44-SD_D3_44") (pintype "bidirectional"))
    )
    (net (code "68") (name "unconnected-(U$1-P45-NFC_URX-Pad45)") (class "Default")
      (node (ref "U$1") (pin "45") (pinfunction "P45-NFC_URX_45") (pintype "bidirectional"))
    )
    (net (code "69") (name "unconnected-(U$1-P46-NFC_UTX-Pad46)") (class "Default")
      (node (ref "U$1") (pin "46") (pinfunction "P46-NFC_UTX_46") (pintype "bidirectional"))
    )
    (net (code "70") (name "unconnected-(U$1-P48-NFC_SWPIO_0-Pad48)") (class "Default")
      (node (ref "U$1") (pin "48") (pinfunction "P48-NFC_SWPIO_0_48") (pintype "bidirectional"))
    )
    (net (code "71") (name "unconnected-(U$1-P49-JTAG_SEL-Pad49)") (class "Default")
      (node (ref "U$1") (pin "49") (pinfunction "P49-JTAG_SEL_49") (pintype "bidirectional"))
    )
    (net (code "72") (name "unconnected-(U$1-P50-WL_REG_ON-Pad50)") (class "Default")
      (node (ref "U$1") (pin "50") (pinfunction "P50-WL_REG_ON_50") (pintype "bidirectional"))
    )
    (net (code "73") (name "unconnected-(U$1-P51-BT_REG_ON-Pad51)") (class "Default")
      (node (ref "U$1") (pin "51") (pinfunction "P51-BT_REG_ON_51") (pintype "bidirectional"))
    )
    (net (code "74") (name "unconnected-(U$1-P53-WL_GPIO1-Pad53)") (class "Default")
      (node (ref "U$1") (pin "53") (pinfunction "P53-WL_GPIO1_53") (pintype "bidirectional"))
    )
    (net (code "75") (name "unconnected-(U$1-P54-WL_GPIO6-Pad54)") (class "Default")
      (node (ref "U$1") (pin "54") (pinfunction "P54-WL_GPIO6_54") (pintype "bidirectional"))
    )
    (net (code "76") (name "unconnected-(U$1-P71-WL_GPIO2-Pad71)") (class "Default")
      (node (ref "U$1") (pin "71") (pinfunction "P71-WL_GPIO2_71") (pintype "bidirectional"))
    )
    (net (code "77") (name "unconnected-(U$1-P72-WL_GPIO3-Pad72)") (class "Default")
      (node (ref "U$1") (pin "72") (pinfunction "P72-WL_GPIO3_72") (pintype "bidirectional"))
    )
    (net (code "78") (name "unconnected-(U$1-P73-WL_GPIO4-Pad73)") (class "Default")
      (node (ref "U$1") (pin "73") (pinfunction "P73-WL_GPIO4_73") (pintype "bidirectional"))
    )
    (net (code "79") (name "unconnected-(U$1-P74-WL_GPIO5-Pad74)") (class "Default")
      (node (ref "U$1") (pin "74") (pinfunction "P74-WL_GPIO5_74") (pintype "bidirectional"))
    )
    (net (code "80") (name "unconnected-(U$1-P75-WL_GPIO12-Pad75)") (class "Default")
      (node (ref "U$1") (pin "75") (pinfunction "P75-WL_GPIO12_75") (pintype "bidirectional"))
    )
    (net (code "81") (name "unconnected-(U$2-BOOT0-Pad60)") (class "Default")
      (node (ref "U$2") (pin "60") (pinfunction "BOOT0_60") (pintype "bidirectional"))
    )
    (net (code "82") (name "unconnected-(U$2-NRST-Pad7)") (class "Default")
      (node (ref "U$2") (pin "7") (pinfunction "NRST_7") (pintype "bidirectional"))
    )
    (net (code "83") (name "unconnected-(U$2-PA0_WKUP-Pad14)") (class "Default")
      (node (ref "U$2") (pin "14") (pinfunction "PA0_WKUP_14") (pintype "bidirectional"))
    )
    (net (code "84") (name "unconnected-(U$2-PA1-Pad15)") (class "Default")
      (node (ref "U$2") (pin "15") (pinfunction "PA1_15") (pintype "bidirectional"))
    )
    (net (code "85") (name "unconnected-(U$2-PA2-Pad16)") (class "Default")
      (node (ref "U$2") (pin "16") (pinfunction "PA2_16") (pintype "bidirectional"))
    )
    (net (code "86") (name "unconnected-(U$2-PA3-Pad17)") (class "Default")
      (node (ref "U$2") (pin "17") (pinfunction "PA3_17") (pintype "bidirectional"))
    )
    (net (code "87") (name "unconnected-(U$2-PA4-Pad20)") (class "Default")
      (node (ref "U$2") (pin "20") (pinfunction "PA4_20") (pintype "bidirectional"))
    )
    (net (code "88") (name "unconnected-(U$2-PA5-Pad21)") (class "Default")
      (node (ref "U$2") (pin "21") (pinfunction "PA5_21") (pintype "bidirectional"))
    )
    (net (code "89") (name "unconnected-(U$2-PA6-Pad22)") (class "Default")
      (node (ref "U$2") (pin "22") (pinfunction "PA6_22") (pintype "bidirectional"))
    )
    (net (code "90") (name "unconnected-(U$2-PA7-Pad23)") (class "Default")
      (node (ref "U$2") (pin "23") (pinfunction "PA7_23") (pintype "bidirectional"))
    )
    (net (code "91") (name "unconnected-(U$2-PA8-Pad41)") (class "Default")
      (node (ref "U$2") (pin "41") (pinfunction "PA8_41") (pintype "bidirectional"))
    )
    (net (code "92") (name "unconnected-(U$2-PA9-Pad42)") (class "Default")
      (node (ref "U$2") (pin "42") (pinfunction "PA9_42") (pintype "bidirectional"))
    )
    (net (code "93") (name "unconnected-(U$2-PA10-Pad43)") (class "Default")
      (node (ref "U$2") (pin "43") (pinfunction "PA10_43") (pintype "bidirectional"))
    )
    (net (code "94") (name "unconnected-(U$2-PA11-Pad44)") (class "Default")
      (node (ref "U$2") (pin "44") (pinfunction "PA11_44") (pintype "bidirectional"))
    )
    (net (code "95") (name "unconnected-(U$2-PA12-Pad45)") (class "Default")
      (node (ref "U$2") (pin "45") (pinfunction "PA12_45") (pintype "bidirectional"))
    )
    (net (code "96") (name "unconnected-(U$2-PA13-Pad46)") (class "Default")
      (node (ref "U$2") (pin "46") (pinfunction "PA13_46") (pintype "bidirectional"))
    )
    (net (code "97") (name "unconnected-(U$2-PA14-Pad49)") (class "Default")
      (node (ref "U$2") (pin "49") (pinfunction "PA14_49") (pintype "bidirectional"))
    )
    (net (code "98") (name "unconnected-(U$2-PA15-Pad50)") (class "Default")
      (node (ref "U$2") (pin "50") (pinfunction "PA15_50") (pintype "bidirectional"))
    )
    (net (code "99") (name "unconnected-(U$2-PB0-Pad26)") (class "Default")
      (node (ref "U$2") (pin "26") (pinfunction "PB0_26") (pintype "bidirectional"))
    )
    (net (code "100") (name "unconnected-(U$2-PB1-Pad27)") (class "Default")
      (node (ref "U$2") (pin "27") (pinfunction "PB1_27") (pintype "bidirectional"))
    )
    (net (code "101") (name "unconnected-(U$2-PB2-Pad28)") (class "Default")
      (node (ref "U$2") (pin "28") (pinfunction "PB2_28") (pintype "bidirectional"))
    )
    (net (code "102") (name "unconnected-(U$2-PB3-Pad55)") (class "Default")
      (node (ref "U$2") (pin "55") (pinfunction "PB3_55") (pintype "bidirectional"))
    )
    (net (code "103") (name "unconnected-(U$2-PB4-Pad56)") (class "Default")
      (node (ref "U$2") (pin "56") (pinfunction "PB4_56") (pintype "bidirectional"))
    )
    (net (code "104") (name "unconnected-(U$2-PB5-Pad57)") (class "Default")
      (node (ref "U$2") (pin "57") (pinfunction "PB5_57") (pintype "bidirectional"))
    )
    (net (code "105") (name "unconnected-(U$2-PB6-Pad58)") (class "Default")
      (node (ref "U$2") (pin "58") (pinfunction "PB6_58") (pintype "bidirectional"))
    )
    (net (code "106") (name "unconnected-(U$2-PB7-Pad59)") (class "Default")
      (node (ref "U$2") (pin "59") (pinfunction "PB7_59") (pintype "bidirectional"))
    )
    (net (code "107") (name "unconnected-(U$2-PB8-Pad61)") (class "Default")
      (node (ref "U$2") (pin "61") (pinfunction "PB8_61") (pintype "bidirectional"))
    )
    (net (code "108") (name "unconnected-(U$2-PB9-Pad62)") (class "Default")
      (node (ref "U$2") (pin "62") (pinfunction "PB9_62") (pintype "bidirectional"))
    )
    (net (code "109") (name "unconnected-(U$2-PB10-Pad29)") (class "Default")
      (node (ref "U$2") (pin "29") (pinfunction "PB10_29") (pintype "bidirectional"))
    )
    (net (code "110") (name "unconnected-(U$2-PB11-Pad30)") (class "Default")
      (node (ref "U$2") (pin "30") (pinfunction "PB11_30") (pintype "bidirectional"))
    )
    (net (code "111") (name "unconnected-(U$2-PB12-Pad33)") (class "Default")
      (node (ref "U$2") (pin "33") (pinfunction "PB12_33") (pintype "bidirectional"))
    )
    (net (code "112") (name "unconnected-(U$2-PB13-Pad34)") (class "Default")
      (node (ref "U$2") (pin "34") (pinfunction "PB13_34") (pintype "bidirectional"))
    )
    (net (code "113") (name "unconnected-(U$2-PB14-Pad35)") (class "Default")
      (node (ref "U$2") (pin "35") (pinfunction "PB14_35") (pintype "bidirectional"))
    )
    (net (code "114") (name "unconnected-(U$2-PB15-Pad36)") (class "Default")
      (node (ref "U$2") (pin "36") (pinfunction "PB15_36") (pintype "bidirectional"))
    )
    (net (code "115") (name "unconnected-(U$2-PC0-Pad8)") (class "Default")
      (node (ref "U$2") (pin "8") (pinfunction "PC0_8") (pintype "bidirectional"))
    )
    (net (code "116") (name "unconnected-(U$2-PC1-Pad9)") (class "Default")
      (node (ref "U$2") (pin "9") (pinfunction "PC1_9") (pintype "bidirectional"))
    )
    (net (code "117") (name "unconnected-(U$2-PC2-Pad10)") (class "Default")
      (node (ref "U$2") (pin "10") (pinfunction "PC2_10") (pintype "bidirectional"))
    )
    (net (code "118") (name "unconnected-(U$2-PC3-Pad11)") (class "Default")
      (node (ref "U$2") (pin "11") (pinfunction "PC3_11") (pintype "bidirectional"))
    )
    (net (code "119") (name "unconnected-(U$2-PC4-Pad24)") (class "Default")
      (node (ref "U$2") (pin "24") (pinfunction "PC4_24") (pintype "bidirectional"))
    )
    (net (code "120") (name "unconnected-(U$2-PC5-Pad25)") (class "Default")
      (node (ref "U$2") (pin "25") (pinfunction "PC5_25") (pintype "bidirectional"))
    )
    (net (code "121") (name "unconnected-(U$2-PC6-Pad37)") (class "Default")
      (node (ref "U$2") (pin "37") (pinfunction "PC6_37") (pintype "bidirectional"))
    )
    (net (code "122") (name "unconnected-(U$2-PC7-Pad38)") (class "Default")
      (node (ref "U$2") (pin "38") (pinfunction "PC7_38") (pintype "bidirectional"))
    )
    (net (code "123") (name "unconnected-(U$2-PC8-Pad39)") (class "Default")
      (node (ref "U$2") (pin "39") (pinfunction "PC8_39") (pintype "bidirectional"))
    )
    (net (code "124") (name "unconnected-(U$2-PC9-Pad40)") (class "Default")
      (node (ref "U$2") (pin "40") (pinfunction "PC9_40") (pintype "bidirectional"))
    )
    (net (code "125") (name "unconnected-(U$2-PC10-Pad51)") (class "Default")
      (node (ref "U$2") (pin "51") (pinfunction "PC10_51") (pintype "bidirectional"))
    )
    (net (code "126") (name "unconnected-(U$2-PC11-Pad52)") (class "Default")
      (node (ref "U$2") (pin "52") (pinfunction "PC11_52") (pintype "bidirectional"))
    )
    (net (code "127") (name "unconnected-(U$2-PC12-Pad53)") (class "Default")
      (node (ref "U$2") (pin "53") (pinfunction "PC12_53") (pintype "bidirectional"))
    )
    (net (code "128") (name "unconnected-(U$2-PC13-Pad2)") (class "Default")
      (node (ref "U$2") (pin "2") (pinfunction "PC13_2") (pintype "bidirectional"))
    )
    (net (code "129") (name "unconnected-(U$2-PC14-Pad3)") (class "Default")
      (node (ref "U$2") (pin "3") (pinfunction "PC14_3") (pintype "bidirectional"))
    )
    (net (code "130") (name "unconnected-(U$2-PC15-Pad4)") (class "Default")
      (node (ref "U$2") (pin "4") (pinfunction "PC15_4") (pintype "bidirectional"))
    )
    (net (code "131") (name "unconnected-(U$2-PD2-Pad54)") (class "Default")
      (node (ref "U$2") (pin "54") (pinfunction "PD2_54") (pintype "bidirectional"))
    )
    (net (code "132") (name "unconnected-(U$2-PH0-Pad5)") (class "Default")
      (node (ref "U$2") (pin "5") (pinfunction "PH0_5") (pintype "bidirectional"))
    )
    (net (code "133") (name "unconnected-(U$2-PH1-Pad6)") (class "Default")
      (node (ref "U$2") (pin "6") (pinfunction "PH1_6") (pintype "bidirectional"))
    )
    (net (code "134") (name "unconnected-(U$2-VBAT-Pad1)") (class "Default")
      (node (ref "U$2") (pin "1") (pinfunction "VBAT_1") (pintype "bidirectional"))
    )
    (net (code "135") (name "unconnected-(U$2-VCAP_1-Pad31)") (class "Default")
      (node (ref "U$2") (pin "31") (pinfunction "VCAP_1_31") (pintype "bidirectional"))
    )
    (net (code "136") (name "unconnected-(U$2-VCAP_2-Pad47)") (class "Default")
      (node (ref "U$2") (pin "47") (pinfunction "VCAP_2_47") (pintype "bidirectional"))
    )
    (net (code "137") (name "unconnected-(U$2-VDD1-Pad64)") (class "Default")
      (node (ref "U$2") (pin "64") (pinfunction "VDD1_64") (pintype "bidirectional"))
    )
    (net (code "138") (name "unconnected-(U$2-VDD2-Pad48)") (class "Default")
      (node (ref "U$2") (pin "48") (pinfunction "VDD2_48") (pintype "bidirectional"))
    )
    (net (code "139") (name "unconnected-(U$2-VDD3-Pad32)") (class "Default")
      (node (ref "U$2") (pin "32") (pinfunction "VDD3_32") (pintype "bidirectional"))
    )
    (net (code "140") (name "unconnected-(U$2-VDD4-Pad19)") (class "Default")
      (node (ref "U$2") (pin "19") (pinfunction "VDD4_19") (pintype "bidirectional"))
    )
    (net (code "141") (name "unconnected-(U$2-VDDA-Pad13)") (class "Default")
      (node (ref "U$2") (pin "13") (pinfunction "VDDA_13") (pintype "bidirectional"))
    )
    (net (code "142") (name "unconnected-(U$2-VSS-Pad18)") (class "Default")
      (node (ref "U$2") (pin "18") (pinfunction "VSS_18") (pintype "bidirectional"))
    )
    (net (code "143") (name "unconnected-(U$2-VSS1-Pad63)") (class "Default")
      (node (ref "U$2") (pin "63") (pinfunction "VSS1_63") (pintype "bidirectional"))
    )
    (net (code "144") (name "unconnected-(U$2-VSSA-Pad12)") (class "Default")
      (node (ref "U$2") (pin "12") (pinfunction "VSSA_12") (pintype "bidirectional"))
    )
    (net (code "145") (name "unconnected-(U1-P08-JTAG_TDRSTN-PadP$8)") (class "Default")
      (node (ref "U1") (pin "P$8") (pinfunction "P08-JTAG_TDRSTN_P$8") (pintype "bidirectional"))
    )
    (net (code "146") (name "unconnected-(U1-P16-WAKEUP-PadP$16)") (class "Default")
      (node (ref "U1") (pin "P$16") (pinfunction "P16-WAKEUP_P$16") (pintype "bidirectional"))
    )
    (net (code "147") (name "unconnected-(U1-P18-USB_DATA_P-PadP$18)") (class "Default")
      (node (ref "U1") (pin "P$18") (pinfunction "P18-USB_DATA_P_P$18") (pintype "bidirectional"))
    )
    (net (code "148") (name "unconnected-(U1-P19-USB_DATA_N-PadP$19)") (class "Default")
      (node (ref "U1") (pin "P$19") (pinfunction "P19-USB_DATA_N_P$19") (pintype "bidirectional"))
    )
    (net (code "149") (name "unconnected-(U1-P21-UART_RX-PadP$21)") (class "Default")
      (node (ref "U1") (pin "P$21") (pinfunction "P21-UART_RX_P$21") (pintype "bidirectional"))
    )
    (net (code "150") (name "unconnected-(U1-P22-UART_TX-PadP$22)") (class "Default")
      (node (ref "U1") (pin "P$22") (pinfunction "P22-UART_TX_P$22") (pintype "bidirectional"))
    )
    (net (code "151") (name "unconnected-(U1-P23-GPIO_0-PadP$23)") (class "Default")
      (node (ref "U1") (pin "P$23") (pinfunction "P23-GPIO_0_P$23") (pintype "bidirectional"))
    )
    (net (code "152") (name "unconnected-(U1-P25-GPIO_2-PadP$25)") (class "Default")
      (node (ref "U1") (pin "P$25") (pinfunction "P25-GPIO_2_P$25") (pintype "bidirectional"))
    )
    (net (code "153") (name "unconnected-(U1-P28-DNC-PadP$28)") (class "Default")
      (node (ref "U1") (pin "P$28") (pinfunction "P28-DNC_P$28") (pintype "bidirectional"))
    )
    (net (code "154") (name "unconnected-(U1-P29-DNC-PadP$29)") (class "Default")
      (node (ref "U1") (pin "P$29") (pinfunction "P29-DNC_P$29") (pintype "bidirectional"))
    )
    (net (code "155") (name "unconnected-(U1-P30-RES{slash}GPIO_15{slash}PB15-PadP$30)") (class "Default")
      (node (ref "U1") (pin "P$30") (pinfunction "P30-RES/GPIO_15/PB15_P$30") (pintype "bidirectional"))
    )
    (net (code "156") (name "unconnected-(U1-P31-RES{slash}GPIO_14{slash}PB14-PadP$31)") (class "Default")
      (node (ref "U1") (pin "P$31") (pinfunction "P31-RES/GPIO_14/PB14_P$31") (pintype "bidirectional"))
    )
    (net (code "157") (name "unconnected-(U1-P32-RES{slash}GPIO_13{slash}PB13-PadP$32)") (class "Default")
      (node (ref "U1") (pin "P$32") (pinfunction "P32-RES/GPIO_13/PB13_P$32") (pintype "bidirectional"))
    )
    (net (code "158") (name "unconnected-(U1-P33-BOOT_0-PadP$33)") (class "Default")
      (node (ref "U1") (pin "P$33") (pinfunction "P33-BOOT_0_P$33") (pintype "bidirectional"))
    )
    (net (code "159") (name "unconnected-(U1-P45-GPIO_A-PadP$45)") (class "Default")
      (node (ref "U1") (pin "P$45") (pinfunction "P45-GPIO_A_P$45") (pintype "bidirectional"))
    )
    (net (code "160") (name "unconnected-(U1-P46-GPIO_B-PadP$46)") (class "Default")
      (node (ref "U1") (pin "P$46") (pinfunction "P46-GPIO_B_P$46") (pintype "bidirectional"))
    )
    (net (code "161") (name "unconnected-(U1-P47-GPIO_C-PadP$47)") (class "Default")
      (node (ref "U1") (pin "P$47") (pinfunction "P47-GPIO_C_P$47") (pintype "bidirectional"))
    )
    (net (code "162") (name "unconnected-(U1-P48-GPIO_D-PadP$48)") (class "Default")
      (node (ref "U1") (pin "P$48") (pinfunction "P48-GPIO_D_P$48") (pintype "bidirectional"))
    )
    (net (code "163") (name "unconnected-(U1-P49-GPIO_E-PadP$49)") (class "Default")
      (node (ref "U1") (pin "P$49") (pinfunction "P49-GPIO_E_P$49") (pintype "bidirectional"))
    )
    (net (code "164") (name "unconnected-(U1-P50-GPIO_F-PadP$50)") (class "Default")
      (node (ref "U1") (pin "P$50") (pinfunction "P50-GPIO_F_P$50") (pintype "bidirectional"))
    )
    (net (code "165") (name "unconnected-(U1-P51-GPIO_G-PadP$51)") (class "Default")
      (node (ref "U1") (pin "P$51") (pinfunction "P51-GPIO_G_P$51") (pintype "bidirectional"))
    )
    (net (code "166") (name "unconnected-(U1-P52-GPIO_H-PadP$52)") (class "Default")
      (node (ref "U1") (pin "P$52") (pinfunction "P52-GPIO_H_P$52") (pintype "bidirectional"))
    )
    (net (code "167") (name "unconnected-(U1-P53-GPIO_I-PadP$53)") (class "Default")
      (node (ref "U1") (pin "P$53") (pinfunction "P53-GPIO_I_P$53") (pintype "bidirectional"))
    )
    (net (code "168") (name "unconnected-(U1-P54-GPIO_K-PadP$54)") (class "Default")
      (node (ref "U1") (pin "P$54") (pinfunction "P54-GPIO_K_P$54") (pintype "bidirectional"))
    )
    (net (code "169") (name "unconnected-(U2-BST-Pad11)") (class "Default")
      (node (ref "U2") (pin "11") (pinfunction "BST_11") (pintype "bidirectional"))
    )
    (net (code "170") (name "unconnected-(U2-VCC-Pad2)") (class "Default")
      (node (ref "U2") (pin "2") (pinfunction "VCC_2") (pintype "bidirectional"))
    )
    (net (code "171") (name "unconnected-(U6-NC1-Pad1)") (class "Default")
      (node (ref "U6") (pin "1") (pinfunction "NC1_1") (pintype "no_connect"))
    )
    (net (code "172") (name "unconnected-(U6-NC2-Pad2)") (class "Default")
      (node (ref "U6") (pin "2") (pinfunction "NC2_2") (pintype "no_connect"))
    )
    (net (code "173") (name "unconnected-(U7-NC1-Pad1)") (class "Default")
      (node (ref "U7") (pin "1") (pinfunction "NC1_1") (pintype "no_connect"))
    )
    (net (code "174") (name "unconnected-(U7-NC2-Pad2)") (class "Default")
      (node (ref "U7") (pin "2") (pinfunction "NC2_2") (pintype "no_connect"))
    )
    (net (code "175") (name "unconnected-(U8-NC1-Pad1)") (class "Default")
      (node (ref "U8") (pin "1") (pinfunction "NC1_1") (pintype "no_connect"))
    )
    (net (code "176") (name "unconnected-(U8-NC2-Pad2)") (class "Default")
      (node (ref "U8") (pin "2") (pinfunction "NC2_2") (pintype "no_connect"))
    )
  )
)
